# C1G14-BreakoutTH.net
KiCad netlist of a schematic drawn in EAGLE
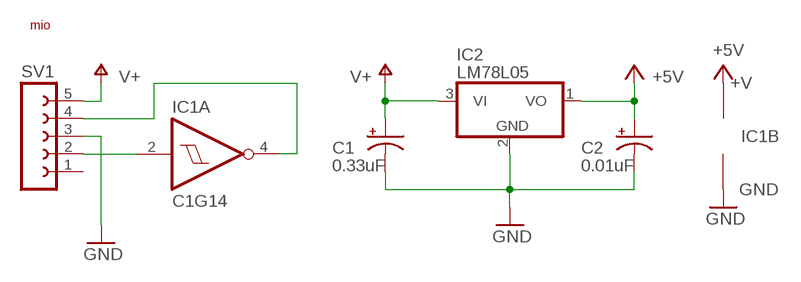
[diagram p0: schematic, sheet 1]

(export (version "E")
  (design (tool "Eeschema 10.0.6"))
  (components
    (comp (ref "C1")
      (value "0.33uF")
      (footprint "eagle-import:E2,5-6")
      (libsource (lib "eagle-import") (part "CPOL-USE2.5-6"))
    )
    (comp (ref "C2")
      (value "0.01uF")
      (footprint "eagle-import:E2,5-6")
      (libsource (lib "eagle-import") (part "CPOL-USE2.5-6"))
    )
    (comp (ref "IC1")
      (value "C1G14")
      (footprint "eagle-import:SOT-25")
      (libsource (lib "eagle-import") (part "C1G14"))
    )
    (comp (ref "IC2")
      (value "LM78L05")
      (footprint "eagle-import:LM78LXX")
      (libsource (lib "eagle-import") (part "LM78L05"))
    )
    (comp (ref "SV1")
      (value "FE05-1")
      (footprint "eagle-import:FE05-1")
      (libsource (lib "eagle-import") (part "FE05-1"))
    )
    (comp (ref "U$2")
      (value "MIO")
      (footprint "eagle-import:MIO")
      (libsource (lib "eagle-import") (part "MIO"))
    )
  )
  (nets
    (net (code "1") (name "+5V") (class "Default")
      (node (ref "C2") (pin "+") (pinfunction "+_+") (pintype "passive"))
      (node (ref "IC1") (pin "5") (pinfunction "V+_5") (pintype "power_in"))
      (node (ref "IC2") (pin "1") (pinfunction "VO_1") (pintype "passive"))
    )
    (net (code "2") (name "GND") (class "Default")
      (node (ref "C1") (pin "-") (pinfunction "-_-") (pintype "passive"))
      (node (ref "C2") (pin "-") (pinfunction "-_-") (pintype "passive"))
      (node (ref "IC1") (pin "3") (pinfunction "GND_3") (pintype "passive"))
      (node (ref "IC2") (pin "2") (pinfunction "GND_2") (pintype "passive"))
      (node (ref "SV1") (pin "3") (pinfunction "3_3") (pintype "passive"))
    )
    (net (code "3") (name "Net-(IC1A-A)") (class "Default")
      (node (ref "IC1") (pin "2") (pinfunction "A_2") (pintype "input"))
      (node (ref "SV1") (pin "2") (pinfunction "2_2") (pintype "passive"))
    )
    (net (code "4") (name "Net-(IC1A-Y)") (class "Default")
      (node (ref "IC1") (pin "4") (pinfunction "Y_4") (pintype "output"))
      (node (ref "SV1") (pin "4") (pinfunction "4_4") (pintype "passive"))
    )
    (net (code "5") (name "V+") (class "Default")
      (node (ref "C1") (pin "+") (pinfunction "+_+") (pintype "passive"))
      (node (ref "IC2") (pin "3") (pinfunction "VI_3") (pintype "input"))
      (node (ref "SV1") (pin "5") (pinfunction "5_5") (pintype "passive"))
    )
    (net (code "6") (name "unconnected-(SV1-Pad1)") (class "Default")
      (node (ref "SV1") (pin "1") (pinfunction "1_1") (pintype "passive"))
    )
  )
)
